# VariablePowerSupply.net
KiCad netlist of a schematic drawn in EAGLE
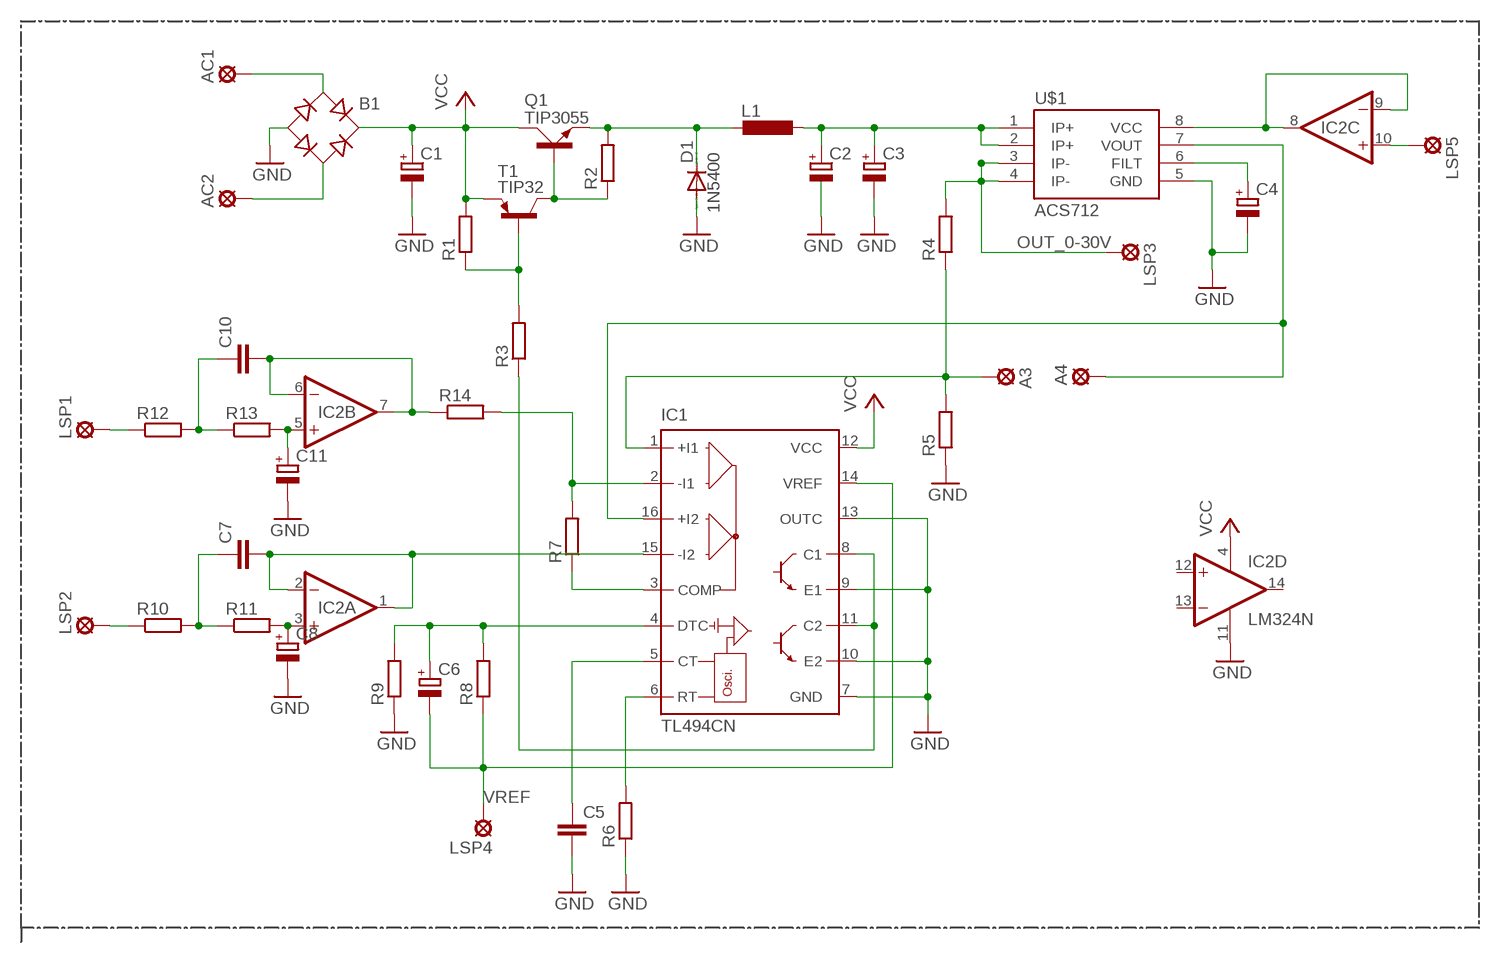
[diagram p0: schematic, sheet 1]

(export (version "E")
  (design (tool "Eeschema 10.0.6"))
  (components
    (comp (ref "A3")
      (value "LSP10")
      (footprint "eagle-import:LSP10")
      (libsource (lib "eagle-import") (part "LSP10"))
    )
    (comp (ref "A4")
      (value "LSP10")
      (footprint "eagle-import:LSP10")
      (libsource (lib "eagle-import") (part "LSP10"))
    )
    (comp (ref "AC1")
      (value "LSP10")
      (footprint "eagle-import:LSP10")
      (libsource (lib "eagle-import") (part "LSP10"))
    )
    (comp (ref "AC2")
      (value "LSP10")
      (footprint "eagle-import:LSP10")
      (libsource (lib "eagle-import") (part "LSP10"))
    )
    (comp (ref "B1")
      (value "DBDB101G")
      (footprint "eagle-import:DB")
      (libsource (lib "eagle-import") (part "DB?GDB101"))
    )
    (comp (ref "C1")
      (value "CPOL-EU085CS-1AR")
      (footprint "eagle-import:085CS_1AR")
      (libsource (lib "eagle-import") (part "CPOL-EU085CS-1AR"))
    )
    (comp (ref "C2")
      (value "CPOL-EU085CS-1AR")
      (footprint "eagle-import:085CS_1AR")
      (libsource (lib "eagle-import") (part "CPOL-EU085CS-1AR"))
    )
    (comp (ref "C3")
      (value "CPOL-EU085CS-1AR")
      (footprint "eagle-import:085CS_1AR")
      (libsource (lib "eagle-import") (part "CPOL-EU085CS-1AR"))
    )
    (comp (ref "C4")
      (value "CPOL-EU085CS-1AR")
      (footprint "eagle-import:085CS_1AR")
      (libsource (lib "eagle-import") (part "CPOL-EU085CS-1AR"))
    )
    (comp (ref "C5")
      (value "C-EU025-025X050")
      (footprint "eagle-import:C025-025X050")
      (libsource (lib "eagle-import") (part "C-EU025-025X050"))
    )
    (comp (ref "C6")
      (value "CPOL-EU085CS-1AR")
      (footprint "eagle-import:085CS_1AR")
      (libsource (lib "eagle-import") (part "CPOL-EU085CS-1AR"))
    )
    (comp (ref "C7")
      (value "C-EU025-025X050")
      (footprint "eagle-import:C025-025X050")
      (libsource (lib "eagle-import") (part "C-EU025-025X050"))
    )
    (comp (ref "C8")
      (value "CPOL-EU085CS-1AR")
      (footprint "eagle-import:085CS_1AR")
      (libsource (lib "eagle-import") (part "CPOL-EU085CS-1AR"))
    )
    (comp (ref "C10")
      (value "C-EU025-025X050")
      (footprint "eagle-import:C025-025X050")
      (libsource (lib "eagle-import") (part "C-EU025-025X050"))
    )
    (comp (ref "C11")
      (value "CPOL-EU085CS-1AR")
      (footprint "eagle-import:085CS_1AR")
      (libsource (lib "eagle-import") (part "CPOL-EU085CS-1AR"))
    )
    (comp (ref "D1")
      (value "1N5400")
      (footprint "eagle-import:DO201-15")
      (libsource (lib "eagle-import") (part "1N5400"))
    )
    (comp (ref "IC1")
      (value "TL494CN")
      (footprint "eagle-import:DIL16")
      (libsource (lib "eagle-import") (part "TL494NC"))
    )
    (comp (ref "IC2")
      (value "LM324N")
      (footprint "eagle-import:DIL14")
      (libsource (lib "eagle-import") (part "LM324N"))
    )
    (comp (ref "L1")
      (value "L-EU0207/10")
      (footprint "eagle-import:0207_10")
      (libsource (lib "eagle-import") (part "L-EU0207/10"))
    )
    (comp (ref "LSP1")
      (value "LSP10")
      (footprint "eagle-import:LSP10")
      (libsource (lib "eagle-import") (part "LSP10"))
    )
    (comp (ref "LSP2")
      (value "LSP10")
      (footprint "eagle-import:LSP10")
      (libsource (lib "eagle-import") (part "LSP10"))
    )
    (comp (ref "LSP3")
      (value "LSP10")
      (footprint "eagle-import:LSP10")
      (libsource (lib "eagle-import") (part "LSP10"))
    )
    (comp (ref "LSP4")
      (value "LSP10")
      (footprint "eagle-import:LSP10")
      (libsource (lib "eagle-import") (part "LSP10"))
    )
    (comp (ref "LSP5")
      (value "LSP10")
      (footprint "eagle-import:LSP10")
      (libsource (lib "eagle-import") (part "LSP10"))
    )
    (comp (ref "Q1")
      (value "TIP3055")
      (footprint "eagle-import:TOP3AV")
      (libsource (lib "eagle-import") (part "TIP3055"))
    )
    (comp (ref "R1")
      (value "R-EU_0204/5")
      (footprint "eagle-import:0204_5")
      (libsource (lib "eagle-import") (part "R-EU_0204/5"))
    )
    (comp (ref "R2")
      (value "R-EU_0204/5")
      (footprint "eagle-import:0204_5")
      (libsource (lib "eagle-import") (part "R-EU_0204/5"))
    )
    (comp (ref "R3")
      (value "R-EU_0204/5")
      (footprint "eagle-import:0204_5")
      (libsource (lib "eagle-import") (part "R-EU_0204/5"))
    )
    (comp (ref "R4")
      (value "R-EU_0204/5")
      (footprint "eagle-import:0204_5")
      (libsource (lib "eagle-import") (part "R-EU_0204/5"))
    )
    (comp (ref "R5")
      (value "R-EU_0204/5")
      (footprint "eagle-import:0204_5")
      (libsource (lib "eagle-import") (part "R-EU_0204/5"))
    )
    (comp (ref "R6")
      (value "R-EU_0204/5")
      (footprint "eagle-import:0204_5")
      (libsource (lib "eagle-import") (part "R-EU_0204/5"))
    )
    (comp (ref "R7")
      (value "R-EU_0204/5")
      (footprint "eagle-import:0204_5")
      (libsource (lib "eagle-import") (part "R-EU_0204/5"))
    )
    (comp (ref "R8")
      (value "R-EU_0204/5")
      (footprint "eagle-import:0204_5")
      (libsource (lib "eagle-import") (part "R-EU_0204/5"))
    )
    (comp (ref "R9")
      (value "R-EU_0204/5")
      (footprint "eagle-import:0204_5")
      (libsource (lib "eagle-import") (part "R-EU_0204/5"))
    )
    (comp (ref "R10")
      (value "R-EU_0204/5")
      (footprint "eagle-import:0204_5")
      (libsource (lib "eagle-import") (part "R-EU_0204/5"))
    )
    (comp (ref "R11")
      (value "R-EU_0204/5")
      (footprint "eagle-import:0204_5")
      (libsource (lib "eagle-import") (part "R-EU_0204/5"))
    )
    (comp (ref "R12")
      (value "R-EU_0204/5")
      (footprint "eagle-import:0204_5")
      (libsource (lib "eagle-import") (part "R-EU_0204/5"))
    )
    (comp (ref "R13")
      (value "R-EU_0204/5")
      (footprint "eagle-import:0204_5")
      (libsource (lib "eagle-import") (part "R-EU_0204/5"))
    )
    (comp (ref "R14")
      (value "R-EU_0204/5")
      (footprint "eagle-import:0204_5")
      (libsource (lib "eagle-import") (part "R-EU_0204/5"))
    )
    (comp (ref "T1")
      (value "TIP32")
      (footprint "eagle-import:TO220")
      (libsource (lib "eagle-import") (part "TIP32"))
    )
    (comp (ref "U$1")
      (value "ACS712")
      (footprint "eagle-import:SO08")
      (libsource (lib "eagle-import") (part "ACS712"))
    )
  )
  (nets
    (net (code "1") (name "/OUT_0-30V") (class "Default")
      (node (ref "LSP3") (pin "MP") (pinfunction "MP_MP") (pintype "passive"))
      (node (ref "R4") (pin "2") (pinfunction "2_2") (pintype "passive"))
      (node (ref "U$1") (pin "3") (pinfunction "IP-_3") (pintype "bidirectional"))
      (node (ref "U$1") (pin "4") (pinfunction "IP-_4") (pintype "bidirectional"))
    )
    (net (code "2") (name "/VREF") (class "Default")
      (node (ref "C6") (pin "-") (pinfunction "-_-") (pintype "passive"))
      (node (ref "IC1") (pin "14") (pinfunction "VREF_14") (pintype "input"))
      (node (ref "LSP4") (pin "MP") (pinfunction "MP_MP") (pintype "passive"))
      (node (ref "R8") (pin "1") (pinfunction "1_1") (pintype "passive"))
    )
    (net (code "3") (name "GND") (class "Default")
      (node (ref "B1") (pin "-") (pinfunction "-_-") (pintype "passive"))
      (node (ref "C1") (pin "-") (pinfunction "-_-") (pintype "passive"))
      (node (ref "C11") (pin "-") (pinfunction "-_-") (pintype "passive"))
      (node (ref "C2") (pin "-") (pinfunction "-_-") (pintype "passive"))
      (node (ref "C3") (pin "-") (pinfunction "-_-") (pintype "passive"))
      (node (ref "C4") (pin "-") (pinfunction "-_-") (pintype "passive"))
      (node (ref "C5") (pin "2") (pinfunction "2_2") (pintype "passive"))
      (node (ref "C8") (pin "-") (pinfunction "-_-") (pintype "passive"))
      (node (ref "D1") (pin "A") (pinfunction "A_A") (pintype "passive"))
      (node (ref "IC1") (pin "10") (pinfunction "E2_10") (pintype "passive"))
      (node (ref "IC1") (pin "13") (pinfunction "OUTC_13") (pintype "output"))
      (node (ref "IC1") (pin "7") (pinfunction "GND_7") (pintype "power_in"))
      (node (ref "IC1") (pin "9") (pinfunction "E1_9") (pintype "passive"))
      (node (ref "IC2") (pin "11") (pinfunction "V-_11") (pintype "power_in"))
      (node (ref "R5") (pin "1") (pinfunction "1_1") (pintype "passive"))
      (node (ref "R6") (pin "1") (pinfunction "1_1") (pintype "passive"))
      (node (ref "R9") (pin "1") (pinfunction "1_1") (pintype "passive"))
      (node (ref "U$1") (pin "5") (pinfunction "GND_5") (pintype "bidirectional"))
    )
    (net (code "4") (name "Net-(AC1-PadMP)") (class "Default")
      (node (ref "AC1") (pin "MP") (pinfunction "MP_MP") (pintype "passive"))
      (node (ref "B1") (pin "AC1") (pinfunction "AC1_AC1") (pintype "passive"))
    )
    (net (code "5") (name "Net-(AC2-PadMP)") (class "Default")
      (node (ref "AC2") (pin "MP") (pinfunction "MP_MP") (pintype "passive"))
      (node (ref "B1") (pin "AC2") (pinfunction "AC2_AC2") (pintype "passive"))
    )
    (net (code "6") (name "Net-(C2-Pad+)") (class "Default")
      (node (ref "C2") (pin "+") (pinfunction "+_+") (pintype "passive"))
      (node (ref "C3") (pin "+") (pinfunction "+_+") (pintype "passive"))
      (node (ref "L1") (pin "1") (pinfunction "1_1") (pintype "passive"))
      (node (ref "U$1") (pin "1") (pinfunction "IP+_1") (pintype "bidirectional"))
      (node (ref "U$1") (pin "2") (pinfunction "IP+_2") (pintype "bidirectional"))
    )
    (net (code "7") (name "Net-(C7-Pad1)") (class "Default")
      (node (ref "C7") (pin "1") (pinfunction "1_1") (pintype "passive"))
      (node (ref "R10") (pin "2") (pinfunction "2_2") (pintype "passive"))
      (node (ref "R11") (pin "1") (pinfunction "1_1") (pintype "passive"))
    )
    (net (code "8") (name "Net-(C10-Pad1)") (class "Default")
      (node (ref "C10") (pin "1") (pinfunction "1_1") (pintype "passive"))
      (node (ref "R12") (pin "2") (pinfunction "2_2") (pintype "passive"))
      (node (ref "R13") (pin "1") (pinfunction "1_1") (pintype "passive"))
    )
    (net (code "9") (name "Net-(D1-PadC)") (class "Default")
      (node (ref "D1") (pin "C") (pinfunction "C_C") (pintype "passive"))
      (node (ref "L1") (pin "2") (pinfunction "2_2") (pintype "passive"))
      (node (ref "Q1") (pin "E") (pinfunction "E_E") (pintype "passive"))
      (node (ref "R2") (pin "2") (pinfunction "2_2") (pintype "passive"))
    )
    (net (code "10") (name "Net-(IC1-+I1)") (class "Default")
      (node (ref "A3") (pin "MP") (pinfunction "MP_MP") (pintype "passive"))
      (node (ref "IC1") (pin "1") (pinfunction "+I1_1") (pintype "input"))
      (node (ref "R4") (pin "1") (pinfunction "1_1") (pintype "passive"))
      (node (ref "R5") (pin "2") (pinfunction "2_2") (pintype "passive"))
    )
    (net (code "11") (name "Net-(IC1-+I2)") (class "Default")
      (node (ref "A4") (pin "MP") (pinfunction "MP_MP") (pintype "passive"))
      (node (ref "IC1") (pin "16") (pinfunction "+I2_16") (pintype "input"))
      (node (ref "U$1") (pin "7") (pinfunction "VOUT_7") (pintype "bidirectional"))
    )
    (net (code "12") (name "Net-(IC1--I1)") (class "Default")
      (node (ref "IC1") (pin "2") (pinfunction "-I1_2") (pintype "input"))
      (node (ref "R14") (pin "2") (pinfunction "2_2") (pintype "passive"))
      (node (ref "R7") (pin "2") (pinfunction "2_2") (pintype "passive"))
    )
    (net (code "13") (name "Net-(IC1--I2)") (class "Default")
      (node (ref "C7") (pin "2") (pinfunction "2_2") (pintype "passive"))
      (node (ref "IC1") (pin "15") (pinfunction "-I2_15") (pintype "input"))
      (node (ref "IC2") (pin "1") (pinfunction "OUT_1") (pintype "output"))
      (node (ref "IC2") (pin "2") (pinfunction "-IN_2") (pintype "input"))
    )
    (net (code "14") (name "Net-(IC1-C1)") (class "Default")
      (node (ref "IC1") (pin "11") (pinfunction "C2_11") (pintype "passive"))
      (node (ref "IC1") (pin "8") (pinfunction "C1_8") (pintype "passive"))
      (node (ref "R3") (pin "1") (pinfunction "1_1") (pintype "passive"))
    )
    (net (code "15") (name "Net-(IC1-COMP)") (class "Default")
      (node (ref "IC1") (pin "3") (pinfunction "COMP_3") (pintype "passive"))
      (node (ref "R7") (pin "1") (pinfunction "1_1") (pintype "passive"))
    )
    (net (code "16") (name "Net-(IC1-CT)") (class "Default")
      (node (ref "C5") (pin "1") (pinfunction "1_1") (pintype "passive"))
      (node (ref "IC1") (pin "5") (pinfunction "CT_5") (pintype "input"))
    )
    (net (code "17") (name "Net-(IC1-DTC)") (class "Default")
      (node (ref "C6") (pin "+") (pinfunction "+_+") (pintype "passive"))
      (node (ref "IC1") (pin "4") (pinfunction "DTC_4") (pintype "input"))
      (node (ref "R8") (pin "2") (pinfunction "2_2") (pintype "passive"))
      (node (ref "R9") (pin "2") (pinfunction "2_2") (pintype "passive"))
    )
    (net (code "18") (name "Net-(IC1-RT)") (class "Default")
      (node (ref "IC1") (pin "6") (pinfunction "RT_6") (pintype "input"))
      (node (ref "R6") (pin "2") (pinfunction "2_2") (pintype "passive"))
    )
    (net (code "19") (name "Net-(IC2A-+IN)") (class "Default")
      (node (ref "C8") (pin "+") (pinfunction "+_+") (pintype "passive"))
      (node (ref "IC2") (pin "3") (pinfunction "+IN_3") (pintype "input"))
      (node (ref "R11") (pin "2") (pinfunction "2_2") (pintype "passive"))
    )
    (net (code "20") (name "Net-(IC2B-+IN)") (class "Default")
      (node (ref "C11") (pin "+") (pinfunction "+_+") (pintype "passive"))
      (node (ref "IC2") (pin "5") (pinfunction "+IN_5") (pintype "input"))
      (node (ref "R13") (pin "2") (pinfunction "2_2") (pintype "passive"))
    )
    (net (code "21") (name "Net-(IC2B--IN)") (class "Default")
      (node (ref "C10") (pin "2") (pinfunction "2_2") (pintype "passive"))
      (node (ref "IC2") (pin "6") (pinfunction "-IN_6") (pintype "input"))
      (node (ref "IC2") (pin "7") (pinfunction "OUT_7") (pintype "output"))
      (node (ref "R14") (pin "1") (pinfunction "1_1") (pintype "passive"))
    )
    (net (code "22") (name "Net-(IC2C-+IN)") (class "Default")
      (node (ref "IC2") (pin "10") (pinfunction "+IN_10") (pintype "input"))
      (node (ref "LSP5") (pin "MP") (pinfunction "MP_MP") (pintype "passive"))
    )
    (net (code "23") (name "Net-(IC2C--IN)") (class "Default")
      (node (ref "IC2") (pin "8") (pinfunction "OUT_8") (pintype "output"))
      (node (ref "IC2") (pin "9") (pinfunction "-IN_9") (pintype "input"))
      (node (ref "U$1") (pin "8") (pinfunction "VCC_8") (pintype "bidirectional"))
    )
    (net (code "24") (name "Net-(LSP1-PadMP)") (class "Default")
      (node (ref "LSP1") (pin "MP") (pinfunction "MP_MP") (pintype "passive"))
      (node (ref "R12") (pin "1") (pinfunction "1_1") (pintype "passive"))
    )
    (net (code "25") (name "Net-(LSP2-PadMP)") (class "Default")
      (node (ref "LSP2") (pin "MP") (pinfunction "MP_MP") (pintype "passive"))
      (node (ref "R10") (pin "1") (pinfunction "1_1") (pintype "passive"))
    )
    (net (code "26") (name "Net-(T1-B)") (class "Default")
      (node (ref "R1") (pin "1") (pinfunction "1_1") (pintype "passive"))
      (node (ref "R3") (pin "2") (pinfunction "2_2") (pintype "passive"))
      (node (ref "T1") (pin "1") (pinfunction "B_1") (pintype "passive"))
    )
    (net (code "27") (name "Net-(T1-C)") (class "Default")
      (node (ref "Q1") (pin "B") (pinfunction "B_B") (pintype "passive"))
      (node (ref "R2") (pin "1") (pinfunction "1_1") (pintype "passive"))
      (node (ref "T1") (pin "2") (pinfunction "C_2") (pintype "passive"))
    )
    (net (code "28") (name "Net-(U$1-FILT)") (class "Default")
      (node (ref "C4") (pin "+") (pinfunction "+_+") (pintype "passive"))
      (node (ref "U$1") (pin "6") (pinfunction "FILT_6") (pintype "bidirectional"))
    )
    (net (code "29") (name "VCC") (class "Default")
      (node (ref "B1") (pin "+") (pinfunction "+_+") (pintype "passive"))
      (node (ref "C1") (pin "+") (pinfunction "+_+") (pintype "passive"))
      (node (ref "IC1") (pin "12") (pinfunction "VCC_12") (pintype "power_in"))
      (node (ref "IC2") (pin "4") (pinfunction "V+_4") (pintype "power_in"))
      (node (ref "Q1") (pin "C") (pinfunction "C_C") (pintype "passive"))
      (node (ref "R1") (pin "2") (pinfunction "2_2") (pintype "passive"))
      (node (ref "T1") (pin "3") (pinfunction "E_3") (pintype "passive"))
    )
    (net (code "30") (name "unconnected-(IC2D-+IN-Pad12)") (class "Default")
      (node (ref "IC2") (pin "12") (pinfunction "+IN_12") (pintype "input"))
    )
    (net (code "31") (name "unconnected-(IC2D--IN-Pad13)") (class "Default")
      (node (ref "IC2") (pin "13") (pinfunction "-IN_13") (pintype "input"))
    )
    (net (code "32") (name "unconnected-(IC2D-OUT-Pad14)") (class "Default")
      (node (ref "IC2") (pin "14") (pinfunction "OUT_14") (pintype "output"))
    )
  )
)
